# PAM8302A.net
KiCad netlist of a schematic drawn in Altium Designer
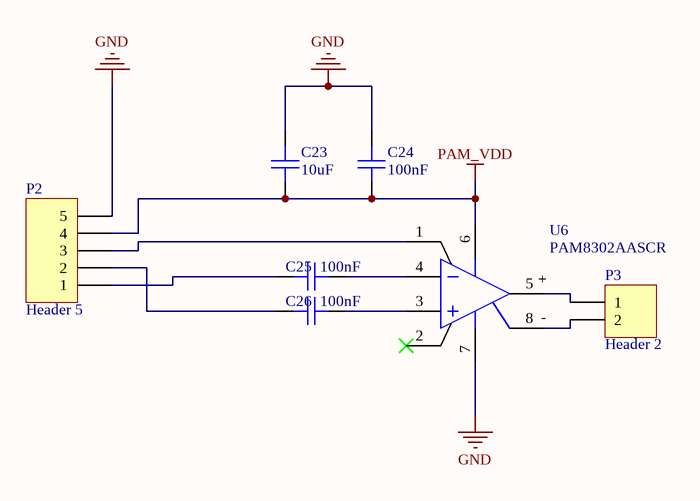
[diagram p0: PAM8302A.SchDoc]

(export (version "E")
  (design (tool "Eeschema 10.0.6"))
  (components
    (comp (ref "C23")
      (value "10uF")
      (footprint "C0603")
      (fields (field (name "NAME") "10uF"))
      (libsource (lib "my_library") (part "CAP_0603"))
    )
    (comp (ref "C24")
      (value "100nF")
      (footprint "C0402")
      (fields (field (name "NAME") "100nF"))
      (libsource (lib "my_library") (part "CAP_0402"))
    )
    (comp (ref "C25")
      (value "100nF")
      (footprint "C0402")
      (fields (field (name "NAME") "100nF"))
      (libsource (lib "my_library") (part "CAP_0402"))
    )
    (comp (ref "C26")
      (value "100nF")
      (footprint "C0402")
      (fields (field (name "NAME") "100nF"))
      (libsource (lib "my_library") (part "CAP_0402"))
    )
    (comp (ref "P2")
      (value "Header 5")
      (footprint "HDR1X5")
      (description "Header, 5-Pin")
      (fields (field (name "PUBLISHER") "Altium Limited"))
      (libsource (lib "Miscellaneous Connectors") (part "Header 5"))
    )
    (comp (ref "P3")
      (value "Header 2")
      (footprint "HDR1X2")
      (description "Header, 2-Pin")
      (fields (field (name "PUBLISHER") "Altium Limited"))
      (libsource (lib "Miscellaneous Connectors") (part "Header 2"))
    )
    (comp (ref "U6")
      (value "PAM8302AASCR")
      (footprint "MSOP-8_L3.0-W3.0-P0.65-LS5.0-BL")
      (fields (field (name "MANUFACTURER") "DIODES(美台)") (field (name "NAME") "PAM8302AASCR"))
      (libsource (lib "my_library") (part "PAM8302AASCR"))
    )
  )
  (nets
    (net (code "1") (name "GND") (class "Default")
      (node (ref "C23") (pin "2") (pinfunction "2_2") (pintype "passive"))
      (node (ref "C24") (pin "2") (pinfunction "2_2") (pintype "passive"))
      (node (ref "P2") (pin "5") (pinfunction "5_5") (pintype "passive"))
      (node (ref "U6") (pin "7") (pinfunction "GND_7") (pintype "passive"))
    )
    (net (code "2") (name "Net-(C25-Pad2)") (class "Default")
      (node (ref "C25") (pin "2") (pinfunction "2_2") (pintype "passive"))
      (node (ref "P2") (pin "1") (pinfunction "1_1") (pintype "passive"))
    )
    (net (code "3") (name "Net-(C26-Pad2)") (class "Default")
      (node (ref "C26") (pin "2") (pinfunction "2_2") (pintype "passive"))
      (node (ref "P2") (pin "2") (pinfunction "2_2") (pintype "passive"))
    )
    (net (code "4") (name "Net-(U6-IN+)") (class "Default")
      (node (ref "C26") (pin "1") (pinfunction "1_1") (pintype "passive"))
      (node (ref "U6") (pin "3") (pinfunction "IN+_3") (pintype "passive"))
    )
    (net (code "5") (name "Net-(U6-IN-)") (class "Default")
      (node (ref "C25") (pin "1") (pinfunction "1_1") (pintype "passive"))
      (node (ref "U6") (pin "4") (pinfunction "IN-_4") (pintype "passive"))
    )
    (net (code "6") (name "Net-(U6-SD#)") (class "Default")
      (node (ref "P2") (pin "3") (pinfunction "3_3") (pintype "passive"))
      (node (ref "U6") (pin "1") (pinfunction "SD#_1") (pintype "passive"))
    )
    (net (code "7") (name "Net-(U6-VO+)") (class "Default")
      (node (ref "P3") (pin "1") (pinfunction "1_1") (pintype "passive"))
      (node (ref "U6") (pin "5") (pinfunction "VO+_5") (pintype "passive"))
    )
    (net (code "8") (name "Net-(U6-VO-)") (class "Default")
      (node (ref "P3") (pin "2") (pinfunction "2_2") (pintype "passive"))
      (node (ref "U6") (pin "8") (pinfunction "VO-_8") (pintype "passive"))
    )
    (net (code "9") (name "PAM_VDD") (class "Default")
      (node (ref "C23") (pin "1") (pinfunction "1_1") (pintype "passive"))
      (node (ref "C24") (pin "1") (pinfunction "1_1") (pintype "passive"))
      (node (ref "P2") (pin "4") (pinfunction "4_4") (pintype "passive"))
      (node (ref "U6") (pin "6") (pinfunction "VDD_6") (pintype "passive"))
    )
    (net (code "10") (name "unconnected-(U6-NC-Pad2)") (class "Default")
      (node (ref "U6") (pin "2") (pinfunction "NC_2") (pintype "passive+no_connect"))
    )
  )
)
